# xmas_lights_rev2.net
KiCad netlist of a schematic drawn in EAGLE
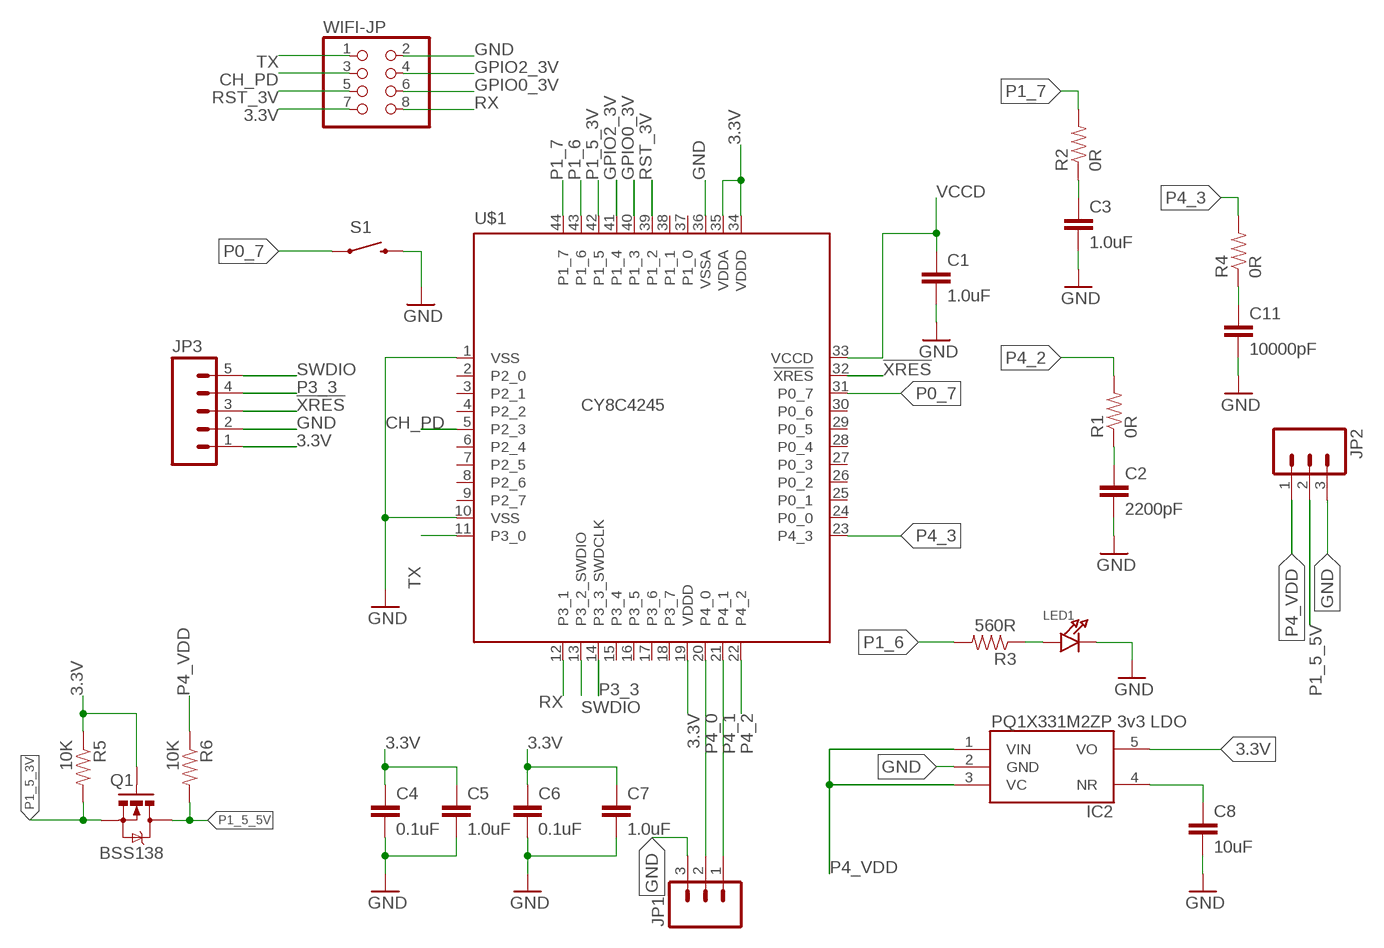
[diagram p0: schematic, sheet 1]

(export (version "E")
  (design (tool "Eeschema 10.0.6"))
  (components
    (comp (ref "C1")
      (value "1.0uF")
      (footprint "eagle-import:0805")
      (libsource (lib "eagle-import") (part "CAP0805"))
    )
    (comp (ref "C2")
      (value "2200pF")
      (footprint "eagle-import:0805")
      (libsource (lib "eagle-import") (part "CAP0805"))
    )
    (comp (ref "C3")
      (value "1.0uF")
      (footprint "eagle-import:0805")
      (libsource (lib "eagle-import") (part "CAP0805"))
    )
    (comp (ref "C4")
      (value "0.1uF")
      (footprint "eagle-import:0805")
      (libsource (lib "eagle-import") (part "CAP0805"))
    )
    (comp (ref "C5")
      (value "1.0uF")
      (footprint "eagle-import:0805")
      (libsource (lib "eagle-import") (part "CAP0805"))
    )
    (comp (ref "C6")
      (value "0.1uF")
      (footprint "eagle-import:0805")
      (libsource (lib "eagle-import") (part "CAP0805"))
    )
    (comp (ref "C7")
      (value "1.0uF")
      (footprint "eagle-import:0805")
      (libsource (lib "eagle-import") (part "CAP0805"))
    )
    (comp (ref "C8")
      (value "10uF")
      (footprint "eagle-import:0805")
      (libsource (lib "eagle-import") (part "CAP0805"))
    )
    (comp (ref "C11")
      (value "10000pF")
      (footprint "eagle-import:0805")
      (libsource (lib "eagle-import") (part "CAP0805"))
    )
    (comp (ref "IC2")
      (value "PQ1X331M2ZP-3V3-LDO-SOT-23-5")
      (footprint "eagle-import:SOT-23-5")
      (libsource (lib "eagle-import") (part "PQ1X331M2ZP-3V3-LDO-SOT-23-5"))
    )
    (comp (ref "JP1")
      (value "M031X03_NO_SILK")
      (footprint "eagle-import:1X03_NO_SILK")
      (libsource (lib "eagle-import") (part "M031X03_NO_SILK"))
    )
    (comp (ref "JP2")
      (value "M031X03_NO_SILK")
      (footprint "eagle-import:1X03_NO_SILK")
      (libsource (lib "eagle-import") (part "M031X03_NO_SILK"))
    )
    (comp (ref "JP3")
      (value "M05PTH")
      (footprint "eagle-import:1X05")
      (libsource (lib "eagle-import") (part "M05PTH"))
    )
    (comp (ref "LED1")
      (value "LED0805")
      (footprint "eagle-import:CHIPLED_0805")
      (libsource (lib "eagle-import") (part "LED0805"))
    )
    (comp (ref "Q1")
      (value "BSS138")
      (footprint "eagle-import:SOT23-3")
      (libsource (lib "eagle-import") (part "MOSFET-NCHANNELSMD"))
    )
    (comp (ref "R1")
      (value "0R")
      (footprint "eagle-import:0805")
      (libsource (lib "eagle-import") (part "SparkFun-Resistors_RESISTOR0805-RES"))
    )
    (comp (ref "R2")
      (value "0R")
      (footprint "eagle-import:0805")
      (libsource (lib "eagle-import") (part "SparkFun-Resistors_RESISTOR0805-RES"))
    )
    (comp (ref "R3")
      (value "560R")
      (footprint "eagle-import:0805")
      (libsource (lib "eagle-import") (part "SparkFun-Resistors_RESISTOR0805-RES"))
    )
    (comp (ref "R4")
      (value "0R")
      (footprint "eagle-import:0805")
      (libsource (lib "eagle-import") (part "SparkFun-Resistors_RESISTOR0805-RES"))
    )
    (comp (ref "R5")
      (value "10K")
      (footprint "eagle-import:0805")
      (libsource (lib "eagle-import") (part "RESISTOR0805-RES"))
    )
    (comp (ref "R6")
      (value "10K")
      (footprint "eagle-import:0805")
      (libsource (lib "eagle-import") (part "RESISTOR0805-RES"))
    )
    (comp (ref "S1")
      (value "SPARKFUN_SWITCH-MOMENTARY-2SMD")
      (footprint "eagle-import:SPARKFUN_TACTILE_SWITCH_SMD")
      (libsource (lib "eagle-import") (part "SPARKFUN_SWITCH-MOMENTARY-2SMD"))
    )
    (comp (ref "U$1")
      (value "CY8C4245")
      (footprint "eagle-import:TQFP44")
      (libsource (lib "eagle-import") (part "CY8C4245AXI-483"))
    )
    (comp (ref "WIFI-JP")
      (value "PINHD-2X4")
      (footprint "eagle-import:2X04")
      (libsource (lib "eagle-import") (part "PINHD-2X4"))
    )
  )
  (nets
    (net (code "1") (name "/CH_PD") (class "Default")
      (node (ref "U$1") (pin "5") (pinfunction "P2_3_5") (pintype "bidirectional"))
      (node (ref "WIFI-JP") (pin "3") (pinfunction "3_3") (pintype "passive"))
    )
    (net (code "2") (name "/GPIO0_3V") (class "Default")
      (node (ref "U$1") (pin "40") (pinfunction "P1_3_40") (pintype "bidirectional"))
      (node (ref "WIFI-JP") (pin "6") (pinfunction "6_6") (pintype "passive"))
    )
    (net (code "3") (name "/GPIO2_3V") (class "Default")
      (node (ref "U$1") (pin "41") (pinfunction "P1_4_41") (pintype "bidirectional"))
      (node (ref "WIFI-JP") (pin "4") (pinfunction "4_4") (pintype "passive"))
    )
    (net (code "4") (name "/P3_3") (class "Default")
      (node (ref "JP3") (pin "4") (pinfunction "4_4") (pintype "passive"))
      (node (ref "U$1") (pin "14") (pinfunction "P3_3_SWDCLK_14") (pintype "bidirectional"))
    )
    (net (code "5") (name "/P4_0") (class "Default")
      (node (ref "JP1") (pin "2") (pinfunction "2_2") (pintype "passive"))
      (node (ref "U$1") (pin "20") (pinfunction "P4_0_20") (pintype "bidirectional"))
    )
    (net (code "6") (name "/P4_1") (class "Default")
      (node (ref "JP1") (pin "1") (pinfunction "1_1") (pintype "passive"))
      (node (ref "U$1") (pin "21") (pinfunction "P4_1_21") (pintype "bidirectional"))
    )
    (net (code "7") (name "/RST_3V") (class "Default")
      (node (ref "U$1") (pin "39") (pinfunction "P1_2_39") (pintype "bidirectional"))
      (node (ref "WIFI-JP") (pin "5") (pinfunction "5_5") (pintype "passive"))
    )
    (net (code "8") (name "/RX") (class "Default")
      (node (ref "U$1") (pin "12") (pinfunction "P3_1_12") (pintype "bidirectional"))
      (node (ref "WIFI-JP") (pin "8") (pinfunction "8_8") (pintype "passive"))
    )
    (net (code "9") (name "/SWDIO") (class "Default")
      (node (ref "JP3") (pin "5") (pinfunction "5_5") (pintype "passive"))
      (node (ref "U$1") (pin "13") (pinfunction "P3_2_SWDIO_13") (pintype "bidirectional"))
    )
    (net (code "10") (name "/TX") (class "Default")
      (node (ref "U$1") (pin "11") (pinfunction "P3_0_11") (pintype "bidirectional"))
      (node (ref "WIFI-JP") (pin "1") (pinfunction "1_1") (pintype "passive"))
    )
    (net (code "11") (name "/VCCD") (class "Default")
      (node (ref "C1") (pin "1") (pinfunction "1_1") (pintype "passive"))
      (node (ref "U$1") (pin "33") (pinfunction "VCCD_33") (pintype "power_in"))
    )
    (net (code "12") (name "/~{XRES}") (class "Default")
      (node (ref "JP3") (pin "3") (pinfunction "3_3") (pintype "passive"))
      (node (ref "U$1") (pin "32") (pinfunction "~{XRES}_32") (pintype "bidirectional"))
    )
    (net (code "13") (name "3.3V") (class "Default")
      (node (ref "C4") (pin "1") (pinfunction "1_1") (pintype "passive"))
      (node (ref "C5") (pin "1") (pinfunction "1_1") (pintype "passive"))
      (node (ref "C6") (pin "1") (pinfunction "1_1") (pintype "passive"))
      (node (ref "C7") (pin "1") (pinfunction "1_1") (pintype "passive"))
      (node (ref "IC2") (pin "5") (pinfunction "VO_5") (pintype "bidirectional"))
      (node (ref "JP3") (pin "1") (pinfunction "1_1") (pintype "passive"))
      (node (ref "Q1") (pin "1") (pinfunction "G_1") (pintype "passive"))
      (node (ref "R5") (pin "1") (pinfunction "1_1") (pintype "passive"))
      (node (ref "U$1") (pin "19") (pinfunction "VDDD_19") (pintype "power_in"))
      (node (ref "U$1") (pin "34") (pinfunction "VDDD_34") (pintype "power_in"))
      (node (ref "U$1") (pin "35") (pinfunction "VDDA_35") (pintype "power_in"))
      (node (ref "WIFI-JP") (pin "7") (pinfunction "7_7") (pintype "passive"))
    )
    (net (code "14") (name "GND") (class "Default")
      (node (ref "C1") (pin "2") (pinfunction "2_2") (pintype "passive"))
      (node (ref "C11") (pin "2") (pinfunction "2_2") (pintype "passive"))
      (node (ref "C2") (pin "2") (pinfunction "2_2") (pintype "passive"))
      (node (ref "C3") (pin "2") (pinfunction "2_2") (pintype "passive"))
      (node (ref "C4") (pin "2") (pinfunction "2_2") (pintype "passive"))
      (node (ref "C5") (pin "2") (pinfunction "2_2") (pintype "passive"))
      (node (ref "C6") (pin "2") (pinfunction "2_2") (pintype "passive"))
      (node (ref "C7") (pin "2") (pinfunction "2_2") (pintype "passive"))
      (node (ref "C8") (pin "2") (pinfunction "2_2") (pintype "passive"))
      (node (ref "IC2") (pin "2") (pinfunction "GND_2") (pintype "bidirectional"))
      (node (ref "JP1") (pin "3") (pinfunction "3_3") (pintype "passive"))
      (node (ref "JP2") (pin "3") (pinfunction "3_3") (pintype "passive"))
      (node (ref "JP3") (pin "2") (pinfunction "2_2") (pintype "passive"))
      (node (ref "LED1") (pin "C") (pinfunction "C_C") (pintype "passive"))
      (node (ref "S1") (pin "3") (pinfunction "2_3") (pintype "passive"))
      (node (ref "U$1") (pin "1") (pinfunction "VSS_1") (pintype "power_in"))
      (node (ref "U$1") (pin "10") (pinfunction "VSS_10") (pintype "power_in"))
      (node (ref "U$1") (pin "36") (pinfunction "VSSA_36") (pintype "power_in"))
      (node (ref "WIFI-JP") (pin "2") (pinfunction "2_2") (pintype "passive"))
    )
    (net (code "15") (name "Net-(C2-Pad1)") (class "Default")
      (node (ref "C2") (pin "1") (pinfunction "1_1") (pintype "passive"))
      (node (ref "R1") (pin "1") (pinfunction "1_1") (pintype "passive"))
    )
    (net (code "16") (name "Net-(C3-Pad1)") (class "Default")
      (node (ref "C3") (pin "1") (pinfunction "1_1") (pintype "passive"))
      (node (ref "R2") (pin "1") (pinfunction "1_1") (pintype "passive"))
    )
    (net (code "17") (name "Net-(C11-Pad1)") (class "Default")
      (node (ref "C11") (pin "1") (pinfunction "1_1") (pintype "passive"))
      (node (ref "R4") (pin "1") (pinfunction "1_1") (pintype "passive"))
    )
    (net (code "18") (name "Net-(IC2-NR)") (class "Default")
      (node (ref "C8") (pin "1") (pinfunction "1_1") (pintype "passive"))
      (node (ref "IC2") (pin "4") (pinfunction "NR_4") (pintype "bidirectional"))
    )
    (net (code "19") (name "Net-(LED1-PadA)") (class "Default")
      (node (ref "LED1") (pin "A") (pinfunction "A_A") (pintype "passive"))
      (node (ref "R3") (pin "1") (pinfunction "1_1") (pintype "passive"))
    )
    (net (code "20") (name "P0_7") (class "Default")
      (node (ref "S1") (pin "1") (pinfunction "1_1") (pintype "passive"))
      (node (ref "U$1") (pin "31") (pinfunction "P0_7_31") (pintype "bidirectional"))
    )
    (net (code "21") (name "P1_5_3V") (class "Default")
      (node (ref "Q1") (pin "2") (pinfunction "S_2") (pintype "passive"))
      (node (ref "R5") (pin "2") (pinfunction "2_2") (pintype "passive"))
      (node (ref "U$1") (pin "42") (pinfunction "P1_5_42") (pintype "bidirectional"))
    )
    (net (code "22") (name "P1_5_5V") (class "Default")
      (node (ref "JP2") (pin "2") (pinfunction "2_2") (pintype "passive"))
      (node (ref "Q1") (pin "3") (pinfunction "D_3") (pintype "passive"))
      (node (ref "R6") (pin "2") (pinfunction "2_2") (pintype "passive"))
    )
    (net (code "23") (name "P1_6") (class "Default")
      (node (ref "R3") (pin "2") (pinfunction "2_2") (pintype "passive"))
      (node (ref "U$1") (pin "43") (pinfunction "P1_6_43") (pintype "bidirectional"))
    )
    (net (code "24") (name "P1_7") (class "Default")
      (node (ref "R2") (pin "2") (pinfunction "2_2") (pintype "passive"))
      (node (ref "U$1") (pin "44") (pinfunction "P1_7_44") (pintype "bidirectional"))
    )
    (net (code "25") (name "P4_2") (class "Default")
      (node (ref "R1") (pin "2") (pinfunction "2_2") (pintype "passive"))
      (node (ref "U$1") (pin "22") (pinfunction "P4_2_22") (pintype "bidirectional"))
    )
    (net (code "26") (name "P4_3") (class "Default")
      (node (ref "R4") (pin "2") (pinfunction "2_2") (pintype "passive"))
      (node (ref "U$1") (pin "23") (pinfunction "P4_3_23") (pintype "bidirectional"))
    )
    (net (code "27") (name "P4_VDD") (class "Default")
      (node (ref "IC2") (pin "1") (pinfunction "VIN_1") (pintype "bidirectional"))
      (node (ref "IC2") (pin "3") (pinfunction "VC_3") (pintype "bidirectional"))
      (node (ref "JP2") (pin "1") (pinfunction "1_1") (pintype "passive"))
      (node (ref "R6") (pin "1") (pinfunction "1_1") (pintype "passive"))
    )
    (net (code "28") (name "unconnected-(U$1-P0_0-Pad24)") (class "Default")
      (node (ref "U$1") (pin "24") (pinfunction "P0_0_24") (pintype "bidirectional"))
    )
    (net (code "29") (name "unconnected-(U$1-P0_1-Pad25)") (class "Default")
      (node (ref "U$1") (pin "25") (pinfunction "P0_1_25") (pintype "bidirectional"))
    )
    (net (code "30") (name "unconnected-(U$1-P0_2-Pad26)") (class "Default")
      (node (ref "U$1") (pin "26") (pinfunction "P0_2_26") (pintype "bidirectional"))
    )
    (net (code "31") (name "unconnected-(U$1-P0_3-Pad27)") (class "Default")
      (node (ref "U$1") (pin "27") (pinfunction "P0_3_27") (pintype "bidirectional"))
    )
    (net (code "32") (name "unconnected-(U$1-P0_4-Pad28)") (class "Default")
      (node (ref "U$1") (pin "28") (pinfunction "P0_4_28") (pintype "bidirectional"))
    )
    (net (code "33") (name "unconnected-(U$1-P0_5-Pad29)") (class "Default")
      (node (ref "U$1") (pin "29") (pinfunction "P0_5_29") (pintype "bidirectional"))
    )
    (net (code "34") (name "unconnected-(U$1-P0_6-Pad30)") (class "Default")
      (node (ref "U$1") (pin "30") (pinfunction "P0_6_30") (pintype "bidirectional"))
    )
    (net (code "35") (name "unconnected-(U$1-P1_0-Pad37)") (class "Default")
      (node (ref "U$1") (pin "37") (pinfunction "P1_0_37") (pintype "bidirectional"))
    )
    (net (code "36") (name "unconnected-(U$1-P1_1-Pad38)") (class "Default")
      (node (ref "U$1") (pin "38") (pinfunction "P1_1_38") (pintype "bidirectional"))
    )
    (net (code "37") (name "unconnected-(U$1-P2_0-Pad2)") (class "Default")
      (node (ref "U$1") (pin "2") (pinfunction "P2_0_2") (pintype "bidirectional"))
    )
    (net (code "38") (name "unconnected-(U$1-P2_1-Pad3)") (class "Default")
      (node (ref "U$1") (pin "3") (pinfunction "P2_1_3") (pintype "bidirectional"))
    )
    (net (code "39") (name "unconnected-(U$1-P2_2-Pad4)") (class "Default")
      (node (ref "U$1") (pin "4") (pinfunction "P2_2_4") (pintype "bidirectional"))
    )
    (net (code "40") (name "unconnected-(U$1-P2_4-Pad6)") (class "Default")
      (node (ref "U$1") (pin "6") (pinfunction "P2_4_6") (pintype "bidirectional"))
    )
    (net (code "41") (name "unconnected-(U$1-P2_5-Pad7)") (class "Default")
      (node (ref "U$1") (pin "7") (pinfunction "P2_5_7") (pintype "bidirectional"))
    )
    (net (code "42") (name "unconnected-(U$1-P2_6-Pad8)") (class "Default")
      (node (ref "U$1") (pin "8") (pinfunction "P2_6_8") (pintype "bidirectional"))
    )
    (net (code "43") (name "unconnected-(U$1-P2_7-Pad9)") (class "Default")
      (node (ref "U$1") (pin "9") (pinfunction "P2_7_9") (pintype "bidirectional"))
    )
    (net (code "44") (name "unconnected-(U$1-P3_4-Pad15)") (class "Default")
      (node (ref "U$1") (pin "15") (pinfunction "P3_4_15") (pintype "bidirectional"))
    )
    (net (code "45") (name "unconnected-(U$1-P3_5-Pad16)") (class "Default")
      (node (ref "U$1") (pin "16") (pinfunction "P3_5_16") (pintype "bidirectional"))
    )
    (net (code "46") (name "unconnected-(U$1-P3_6-Pad17)") (class "Default")
      (node (ref "U$1") (pin "17") (pinfunction "P3_6_17") (pintype "bidirectional"))
    )
    (net (code "47") (name "unconnected-(U$1-P3_7-Pad18)") (class "Default")
      (node (ref "U$1") (pin "18") (pinfunction "P3_7_18") (pintype "bidirectional"))
    )
  )
)
